# MDQARM_COIL.net
KiCad netlist of a schematic drawn in Altium Designer
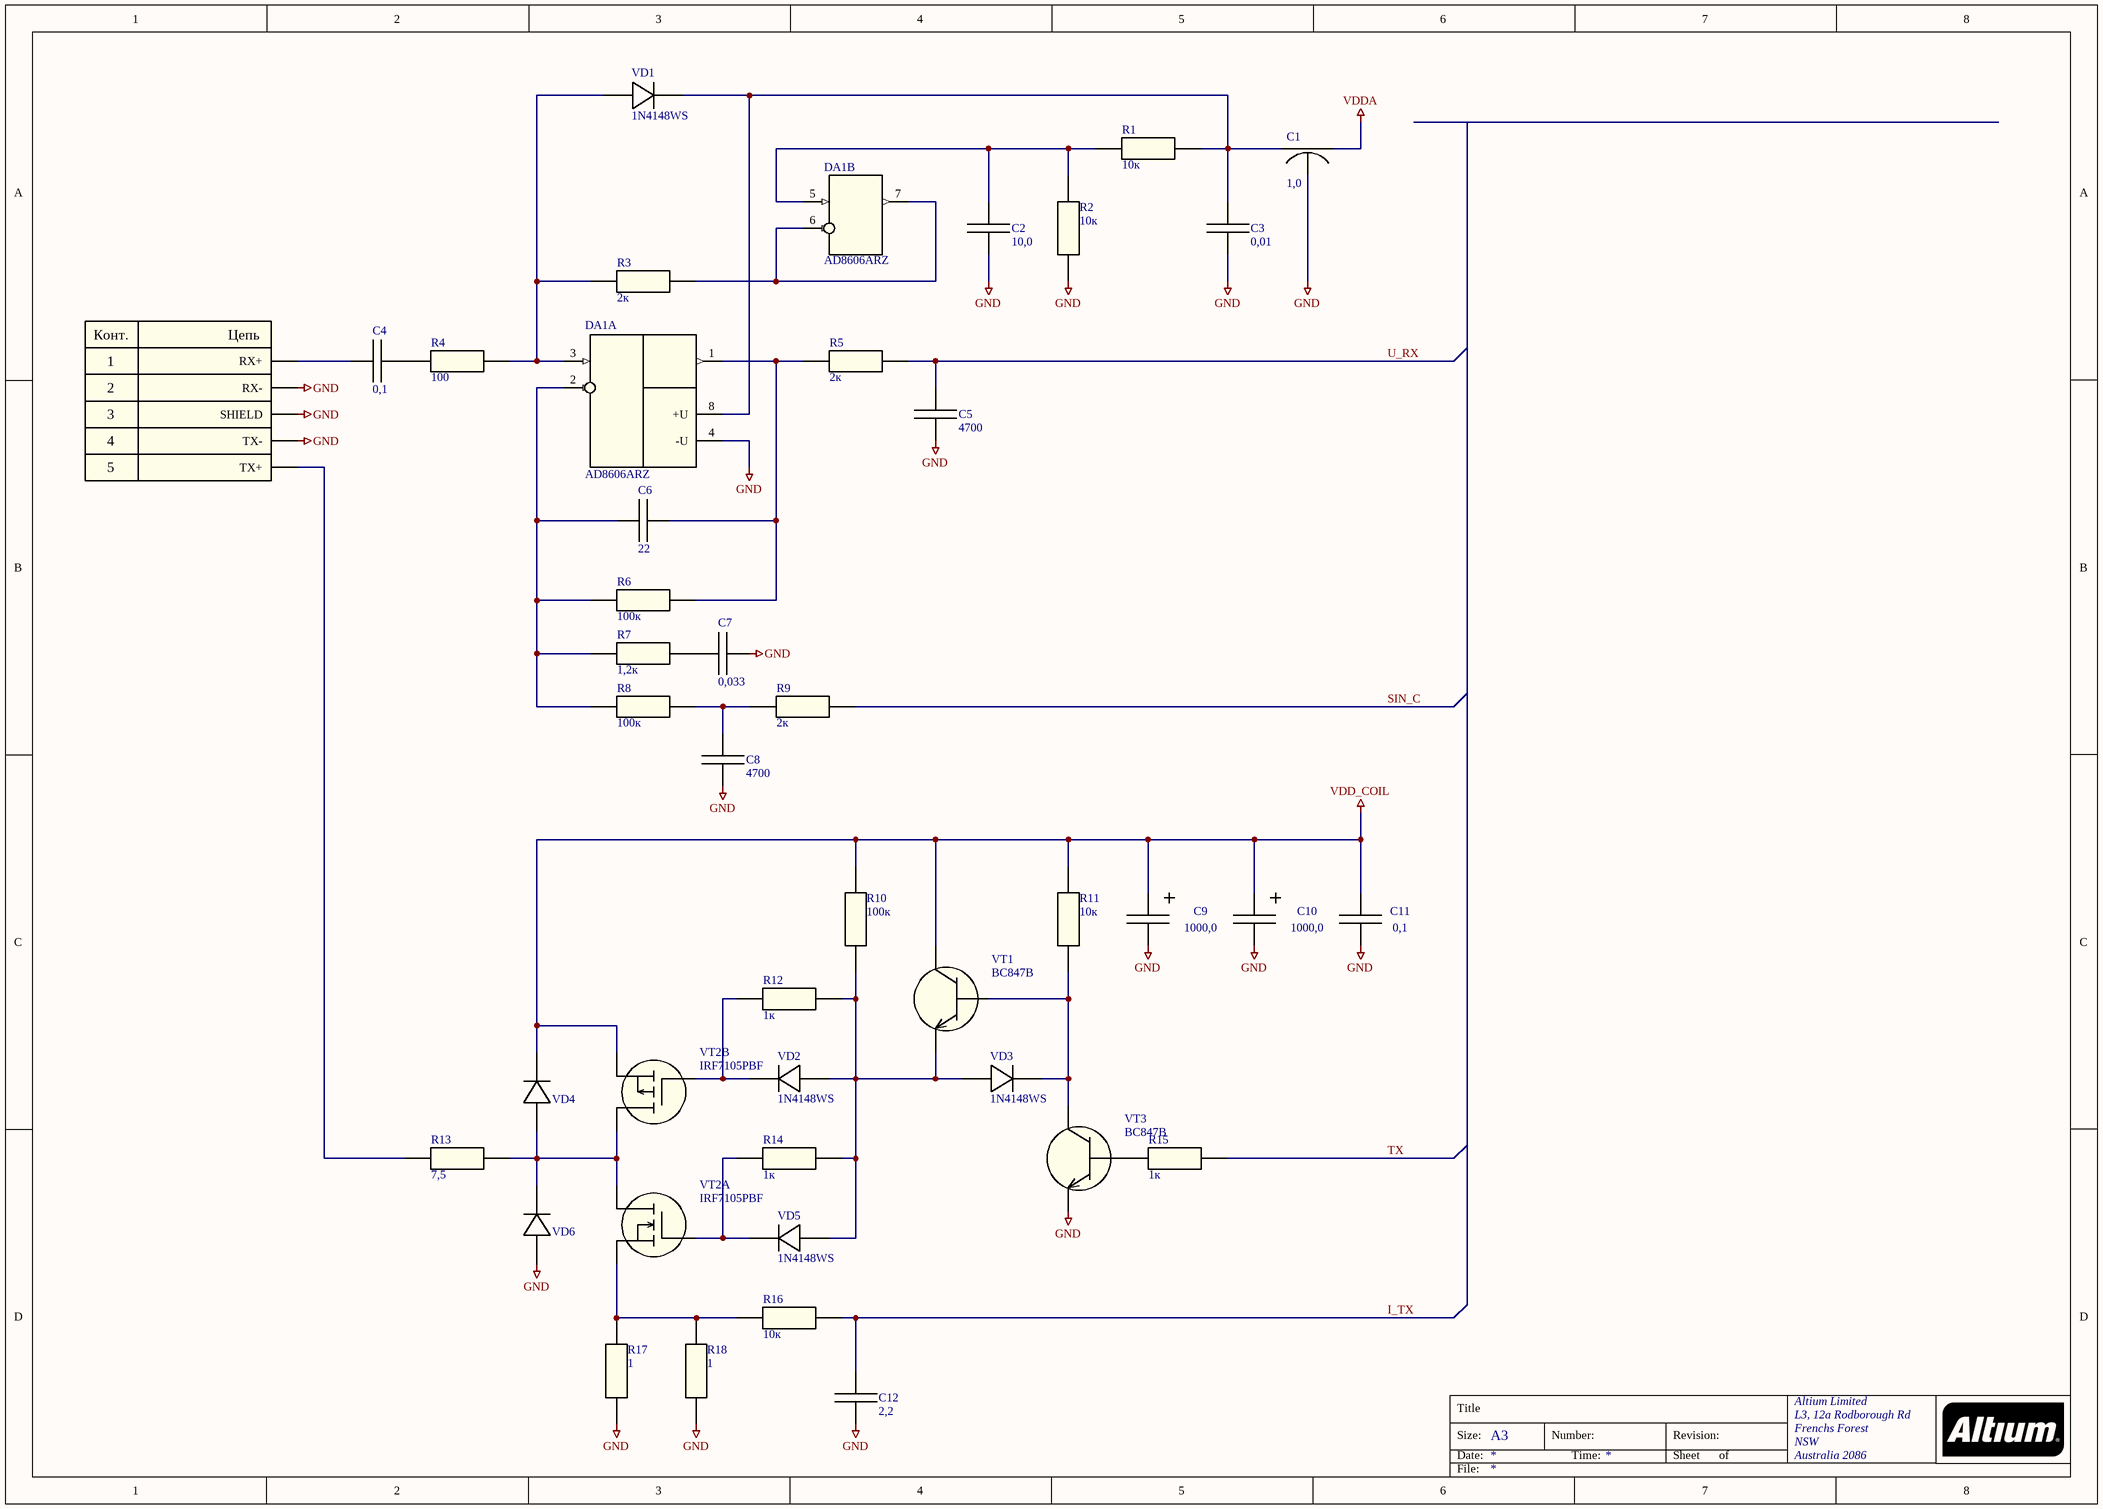
[diagram p0: MDQARM_COIL.SchDoc]

(export (version "E")
  (design (tool "Eeschema 10.0.6"))
  (components
    (comp (ref "*1")
      (value "Connector MD_COIL")
      (footprint "Connector MD_COIL")
      (libsource (lib "IVV_Connectors") (part "Connector MD_COIL"))
    )
    (comp (ref "C1")
      (value "1,0")
      (footprint "Filter NFM21PC")
      (libsource (lib "IVV_Passive") (part "Filter NFM21PC105B1С3D"))
    )
    (comp (ref "C2")
      (value "10,0")
      (footprint "Capacitor SMD0805-T1.35")
      (libsource (lib "IVV_Passive") (part "Capacitor C0805_10u"))
    )
    (comp (ref "C3")
      (value "0,01")
      (footprint "Capacitor SMD0805-T0.75")
      (libsource (lib "IVV_Passive") (part "Capacitor C0805_10n"))
    )
    (comp (ref "C4")
      (value "0,1")
      (footprint "Capacitor SMD0805_5mm")
      (libsource (lib "IVV_Passive") (part "Capacitor C0805_5mm_100n"))
    )
    (comp (ref "C5")
      (value "4700")
      (footprint "Capacitor SMD0805-T0.75")
      (libsource (lib "IVV_Passive") (part "Capacitor C0805_4.7n"))
    )
    (comp (ref "C6")
      (value "22")
      (footprint "Capacitor SMD0805-T0.75")
      (libsource (lib "IVV_Passive") (part "Capacitor C0805_22p"))
    )
    (comp (ref "C7")
      (value "0,033")
      (footprint "Capacitor SMD0805_5mm")
      (libsource (lib "IVV_Passive") (part "Capacitor C0805_5mm_33n"))
    )
    (comp (ref "C8")
      (value "4700")
      (footprint "Capacitor SMD0805-T0.75")
      (libsource (lib "IVV_Passive") (part "Capacitor C0805_4.7n"))
    )
    (comp (ref "C9")
      (value "1000,0")
      (footprint "Capacitor ECAP SMD10x10.5")
      (libsource (lib "IVV_Passive") (part "Capacitor ECAP SMD 1000uF_6.3V"))
    )
    (comp (ref "C10")
      (value "1000,0")
      (footprint "Capacitor ECAP SMD10x10.5")
      (libsource (lib "IVV_Passive") (part "Capacitor ECAP SMD 1000uF_6.3V"))
    )
    (comp (ref "C11")
      (value "0,1")
      (footprint "Capacitor SMD0805-T0.95")
      (libsource (lib "IVV_Passive") (part "Capacitor C0805_100n"))
    )
    (comp (ref "C12")
      (value "2,2")
      (footprint "Capacitor SMD0805-T1.35")
      (libsource (lib "IVV_Passive") (part "Capacitor C0805_2.2u"))
    )
    (comp (ref "DA1")
      (value "AD8606ARZ")
      (footprint "IC AD8606ARZ")
      (libsource (lib "IVV_IC") (part "IC AD8606ARZ"))
    )
    (comp (ref "R1")
      (value "10к")
      (footprint "Resistor SMD0805")
      (libsource (lib "IVV_Passive") (part "Resistor R0805_10k_1%"))
    )
    (comp (ref "R2")
      (value "10к")
      (footprint "Resistor SMD0805")
      (libsource (lib "") (part "Resistor R0805_10k_1%_1"))
    )
    (comp (ref "R3")
      (value "2к")
      (footprint "Resistor SMD0805")
      (libsource (lib "IVV_Passive") (part "Resistor R0805_2k_1%"))
    )
    (comp (ref "R4")
      (value "100")
      (footprint "Resistor SMD0805")
      (libsource (lib "IVV_Passive") (part "Resistor R0805_100_1%"))
    )
    (comp (ref "R5")
      (value "2к")
      (footprint "Resistor SMD0805")
      (libsource (lib "") (part "Resistor R0805_2k_5%_1"))
    )
    (comp (ref "R6")
      (value "100к")
      (footprint "Resistor SMD0805")
      (libsource (lib "") (part "Resistor R0805_100k_1%_1"))
    )
    (comp (ref "R7")
      (value "1,2к")
      (footprint "Resistor SMD0805")
      (libsource (lib "IVV_Passive") (part "Resistor R0805_1.2k_1%"))
    )
    (comp (ref "R8")
      (value "100к")
      (footprint "Resistor SMD0805")
      (libsource (lib "IVV_Passive") (part "Resistor R0805_100k_1%"))
    )
    (comp (ref "R9")
      (value "2к")
      (footprint "Resistor SMD0805")
      (libsource (lib "IVV_Passive") (part "Resistor R0805_2k_5%"))
    )
    (comp (ref "R10")
      (value "100к")
      (footprint "Resistor SMD0805")
      (libsource (lib "IVV_Passive") (part "Resistor R0805_100k_5%"))
    )
    (comp (ref "R11")
      (value "10к")
      (footprint "Resistor SMD0805")
      (libsource (lib "") (part "Resistor R0805_10k_5%_1"))
    )
    (comp (ref "R12")
      (value "1к")
      (footprint "Resistor SMD0805")
      (libsource (lib "IVV_Passive") (part "Resistor R0805_1k_5%"))
    )
    (comp (ref "R13")
      (value "7,5")
      (footprint "Resistor SMD2512")
      (libsource (lib "IVV_Passive") (part "Resistor R2512_7.5R_5%"))
    )
    (comp (ref "R14")
      (value "1к")
      (footprint "Resistor SMD0805")
      (libsource (lib "IVV_Passive") (part "Resistor R0805_1k_5%"))
    )
    (comp (ref "R15")
      (value "1к")
      (footprint "Resistor SMD0805")
      (libsource (lib "IVV_Passive") (part "Resistor R0805_1k_5%"))
    )
    (comp (ref "R16")
      (value "10к")
      (footprint "Resistor SMD0805")
      (libsource (lib "IVV_Passive") (part "Resistor R0805_10k_5%"))
    )
    (comp (ref "R17")
      (value "1")
      (footprint "Resistor SMD1206")
      (libsource (lib "IVV_Passive") (part "Resistor R1206_1R_5%"))
    )
    (comp (ref "R18")
      (value "1")
      (footprint "Resistor SMD1206")
      (libsource (lib "IVV_Passive") (part "Resistor R1206_1R_5%"))
    )
    (comp (ref "VD1")
      (value "1N4148WS")
      (footprint "Diode SOD-323")
      (description "150mA 100V 4ns")
      (libsource (lib "IVV_Lib") (part "Diode 1N4148WS"))
    )
    (comp (ref "VD2")
      (value "1N4148WS")
      (footprint "Diode SOD-323")
      (description "150mA 100V 4ns")
      (libsource (lib "IVV_Lib") (part "Diode 1N4148WS"))
    )
    (comp (ref "VD3")
      (value "1N4148WS")
      (footprint "Diode SOD-323")
      (description "150mA 100V 4ns")
      (libsource (lib "IVV_Lib") (part "Diode 1N4148WS"))
    )
    (comp (ref "VD4")
      (value "ES1J")
      (footprint "Diode SMA")
      (description "1A 600V 35ns")
      (libsource (lib "IVV_Lib") (part "Diode ES1J"))
    )
    (comp (ref "VD5")
      (value "1N4148WS")
      (footprint "Diode SOD-323")
      (description "150mA 100V 4ns")
      (libsource (lib "IVV_Lib") (part "Diode 1N4148WS"))
    )
    (comp (ref "VD6")
      (value "ES1J")
      (footprint "Diode SMA")
      (description "1A 600V 35ns")
      (libsource (lib "IVV_Lib") (part "Diode ES1J"))
    )
    (comp (ref "VT1")
      (value "BC847B")
      (footprint "Transistor SOT23")
      (libsource (lib "IVV_Lib") (part "Transistor BC847B"))
    )
    (comp (ref "VT2")
      (value "IRF7105PBF")
      (footprint "Transisror IRF7105")
      (libsource (lib "IVV_Lib") (part "Transistor IRF7105PBF"))
    )
    (comp (ref "VT3")
      (value "BC847B")
      (footprint "Transistor SOT23")
      (libsource (lib "IVV_Lib") (part "Transistor BC847B"))
    )
  )
  (nets
    (net (code "1") (name "/I_TX") (class "Default")
      (node (ref "C12") (pin "2") (pinfunction "2_2") (pintype "passive"))
      (node (ref "R16") (pin "2") (pinfunction "2_2") (pintype "passive"))
    )
    (net (code "2") (name "/SIN_C") (class "Default")
      (node (ref "R9") (pin "1") (pinfunction "1_1") (pintype "passive"))
    )
    (net (code "3") (name "/TX") (class "Default")
      (node (ref "R15") (pin "2") (pinfunction "2_2") (pintype "passive"))
    )
    (net (code "4") (name "/U_RX") (class "Default")
      (node (ref "C5") (pin "2") (pinfunction "2_2") (pintype "passive"))
      (node (ref "R5") (pin "2") (pinfunction "2_2") (pintype "passive"))
    )
    (net (code "5") (name "GND") (class "Default")
      (node (ref "*1") (pin "2") (pinfunction "RX-_2") (pintype "passive"))
      (node (ref "*1") (pin "3") (pinfunction "SHIELD_3") (pintype "passive"))
      (node (ref "*1") (pin "4") (pinfunction "TX-_4") (pintype "passive"))
      (node (ref "C1") (pin "2") (pinfunction "2_2") (pintype "passive"))
      (node (ref "C10") (pin "2") (pinfunction "2_2") (pintype "passive"))
      (node (ref "C11") (pin "2") (pinfunction "2_2") (pintype "passive"))
      (node (ref "C12") (pin "1") (pinfunction "1_1") (pintype "passive"))
      (node (ref "C2") (pin "1") (pinfunction "1_1") (pintype "passive"))
      (node (ref "C3") (pin "1") (pinfunction "1_1") (pintype "passive"))
      (node (ref "C5") (pin "1") (pinfunction "1_1") (pintype "passive"))
      (node (ref "C7") (pin "1") (pinfunction "1_1") (pintype "passive"))
      (node (ref "C8") (pin "1") (pinfunction "1_1") (pintype "passive"))
      (node (ref "C9") (pin "2") (pinfunction "2_2") (pintype "passive"))
      (node (ref "DA1") (pin "4") (pinfunction "-U_4") (pintype "power_in"))
      (node (ref "R17") (pin "1") (pinfunction "1_1") (pintype "passive"))
      (node (ref "R18") (pin "1") (pinfunction "1_1") (pintype "passive"))
      (node (ref "R2") (pin "1") (pinfunction "1_1") (pintype "passive"))
      (node (ref "VD6") (pin "1") (pinfunction "A_1") (pintype "passive"))
      (node (ref "VT3") (pin "2") (pinfunction "E_2") (pintype "passive"))
    )
    (net (code "6") (name "Net-(*1-RX+)") (class "Default")
      (node (ref "*1") (pin "1") (pinfunction "RX+_1") (pintype "passive"))
      (node (ref "C4") (pin "2") (pinfunction "2_2") (pintype "passive"))
    )
    (net (code "7") (name "Net-(*1-TX+)") (class "Default")
      (node (ref "*1") (pin "5") (pinfunction "TX+_5") (pintype "passive"))
      (node (ref "R13") (pin "1") (pinfunction "1_1") (pintype "passive"))
    )
    (net (code "8") (name "Net-(C4-Pad1)") (class "Default")
      (node (ref "C4") (pin "1") (pinfunction "1_1") (pintype "passive"))
      (node (ref "R4") (pin "1") (pinfunction "1_1") (pintype "passive"))
    )
    (net (code "9") (name "Net-(C7-Pad2)") (class "Default")
      (node (ref "C7") (pin "2") (pinfunction "2_2") (pintype "passive"))
      (node (ref "R7") (pin "2") (pinfunction "2_2") (pintype "passive"))
    )
    (net (code "10") (name "Net-(C8-Pad2)") (class "Default")
      (node (ref "C8") (pin "2") (pinfunction "2_2") (pintype "passive"))
      (node (ref "R8") (pin "1") (pinfunction "1_1") (pintype "passive"))
      (node (ref "R9") (pin "2") (pinfunction "2_2") (pintype "passive"))
    )
    (net (code "11") (name "Net-(DA1A-+INA)") (class "Default")
      (node (ref "DA1") (pin "3") (pinfunction "+INA_3") (pintype "input"))
      (node (ref "R3") (pin "1") (pinfunction "1_1") (pintype "passive"))
      (node (ref "R4") (pin "2") (pinfunction "2_2") (pintype "passive"))
      (node (ref "VD1") (pin "1") (pinfunction "A_1") (pintype "passive"))
    )
    (net (code "12") (name "Net-(DA1A-+U)") (class "Default")
      (node (ref "C1") (pin "1") (pinfunction "1_1") (pintype "passive"))
      (node (ref "C3") (pin "2") (pinfunction "2_2") (pintype "passive"))
      (node (ref "DA1") (pin "8") (pinfunction "+U_8") (pintype "power_in"))
      (node (ref "R1") (pin "2") (pinfunction "2_2") (pintype "passive"))
      (node (ref "VD1") (pin "2") (pinfunction "C_2") (pintype "passive"))
    )
    (net (code "13") (name "Net-(DA1A--INA)") (class "Default")
      (node (ref "C6") (pin "1") (pinfunction "1_1") (pintype "passive"))
      (node (ref "DA1") (pin "2") (pinfunction "-INA_2") (pintype "input"))
      (node (ref "R6") (pin "1") (pinfunction "1_1") (pintype "passive"))
      (node (ref "R7") (pin "1") (pinfunction "1_1") (pintype "passive"))
      (node (ref "R8") (pin "2") (pinfunction "2_2") (pintype "passive"))
    )
    (net (code "14") (name "Net-(DA1A-OUTA)") (class "Default")
      (node (ref "C6") (pin "2") (pinfunction "2_2") (pintype "passive"))
      (node (ref "DA1") (pin "1") (pinfunction "OUTA_1") (pintype "output"))
      (node (ref "R5") (pin "1") (pinfunction "1_1") (pintype "passive"))
      (node (ref "R6") (pin "2") (pinfunction "2_2") (pintype "passive"))
    )
    (net (code "15") (name "Net-(DA1B-INB+)") (class "Default")
      (node (ref "C2") (pin "2") (pinfunction "2_2") (pintype "passive"))
      (node (ref "DA1") (pin "5") (pinfunction "INB+_5") (pintype "input"))
      (node (ref "R1") (pin "1") (pinfunction "1_1") (pintype "passive"))
      (node (ref "R2") (pin "2") (pinfunction "2_2") (pintype "passive"))
    )
    (net (code "16") (name "Net-(DA1B-INB-)") (class "Default")
      (node (ref "DA1") (pin "6") (pinfunction "INB-_6") (pintype "input"))
      (node (ref "DA1") (pin "7") (pinfunction "OUTB_7") (pintype "output"))
      (node (ref "R3") (pin "2") (pinfunction "2_2") (pintype "passive"))
    )
    (net (code "17") (name "Net-(R16-Pad1)") (class "Default")
      (node (ref "R16") (pin "1") (pinfunction "1_1") (pintype "passive"))
      (node (ref "R17") (pin "2") (pinfunction "2_2") (pintype "passive"))
      (node (ref "R18") (pin "2") (pinfunction "2_2") (pintype "passive"))
      (node (ref "VT2") (pin "S1") (pinfunction "S1_S1") (pintype "passive"))
    )
    (net (code "18") (name "Net-(VD2-A)") (class "Default")
      (node (ref "R10") (pin "1") (pinfunction "1_1") (pintype "passive"))
      (node (ref "R12") (pin "2") (pinfunction "2_2") (pintype "passive"))
      (node (ref "R14") (pin "2") (pinfunction "2_2") (pintype "passive"))
      (node (ref "VD2") (pin "1") (pinfunction "A_1") (pintype "passive"))
      (node (ref "VD3") (pin "1") (pinfunction "A_1") (pintype "passive"))
      (node (ref "VD5") (pin "1") (pinfunction "A_1") (pintype "passive"))
      (node (ref "VT1") (pin "2") (pinfunction "E_2") (pintype "passive"))
    )
    (net (code "19") (name "Net-(VD2-C)") (class "Default")
      (node (ref "R12") (pin "1") (pinfunction "1_1") (pintype "passive"))
      (node (ref "VD2") (pin "2") (pinfunction "C_2") (pintype "passive"))
      (node (ref "VT2") (pin "G2") (pinfunction "G2_G2") (pintype "passive"))
    )
    (net (code "20") (name "Net-(VD3-C)") (class "Default")
      (node (ref "R11") (pin "1") (pinfunction "1_1") (pintype "passive"))
      (node (ref "VD3") (pin "2") (pinfunction "C_2") (pintype "passive"))
      (node (ref "VT1") (pin "1") (pinfunction "B_1") (pintype "passive"))
      (node (ref "VT3") (pin "3") (pinfunction "C_3") (pintype "passive"))
    )
    (net (code "21") (name "Net-(VD4-A)") (class "Default")
      (node (ref "R13") (pin "2") (pinfunction "2_2") (pintype "passive"))
      (node (ref "VD4") (pin "1") (pinfunction "A_1") (pintype "passive"))
      (node (ref "VD6") (pin "2") (pinfunction "C_2") (pintype "passive"))
      (node (ref "VT2") (pin "D1") (pinfunction "D1_D1") (pintype "passive"))
      (node (ref "VT2") (pin "D2") (pinfunction "D2_D2") (pintype "passive"))
    )
    (net (code "22") (name "Net-(VD5-C)") (class "Default")
      (node (ref "R14") (pin "1") (pinfunction "1_1") (pintype "passive"))
      (node (ref "VD5") (pin "2") (pinfunction "C_2") (pintype "passive"))
      (node (ref "VT2") (pin "G1") (pinfunction "G1_G1") (pintype "passive"))
    )
    (net (code "23") (name "Net-(VT3-B)") (class "Default")
      (node (ref "R15") (pin "1") (pinfunction "1_1") (pintype "passive"))
      (node (ref "VT3") (pin "1") (pinfunction "B_1") (pintype "passive"))
    )
    (net (code "24") (name "VDDA") (class "Default")
      (node (ref "C1") (pin "3") (pinfunction "3_3") (pintype "passive"))
    )
    (net (code "25") (name "VDD_COIL") (class "Default")
      (node (ref "C10") (pin "1") (pinfunction "1_1") (pintype "passive"))
      (node (ref "C11") (pin "1") (pinfunction "1_1") (pintype "passive"))
      (node (ref "C9") (pin "1") (pinfunction "1_1") (pintype "passive"))
      (node (ref "R10") (pin "2") (pinfunction "2_2") (pintype "passive"))
      (node (ref "R11") (pin "2") (pinfunction "2_2") (pintype "passive"))
      (node (ref "VD4") (pin "2") (pinfunction "C_2") (pintype "passive"))
      (node (ref "VT1") (pin "3") (pinfunction "C_3") (pintype "passive"))
      (node (ref "VT2") (pin "S2") (pinfunction "S2_S2") (pintype "passive"))
    )
  )
)
